# ESP_DCF77_Emulator.net
KiCad netlist of a schematic drawn in EAGLE
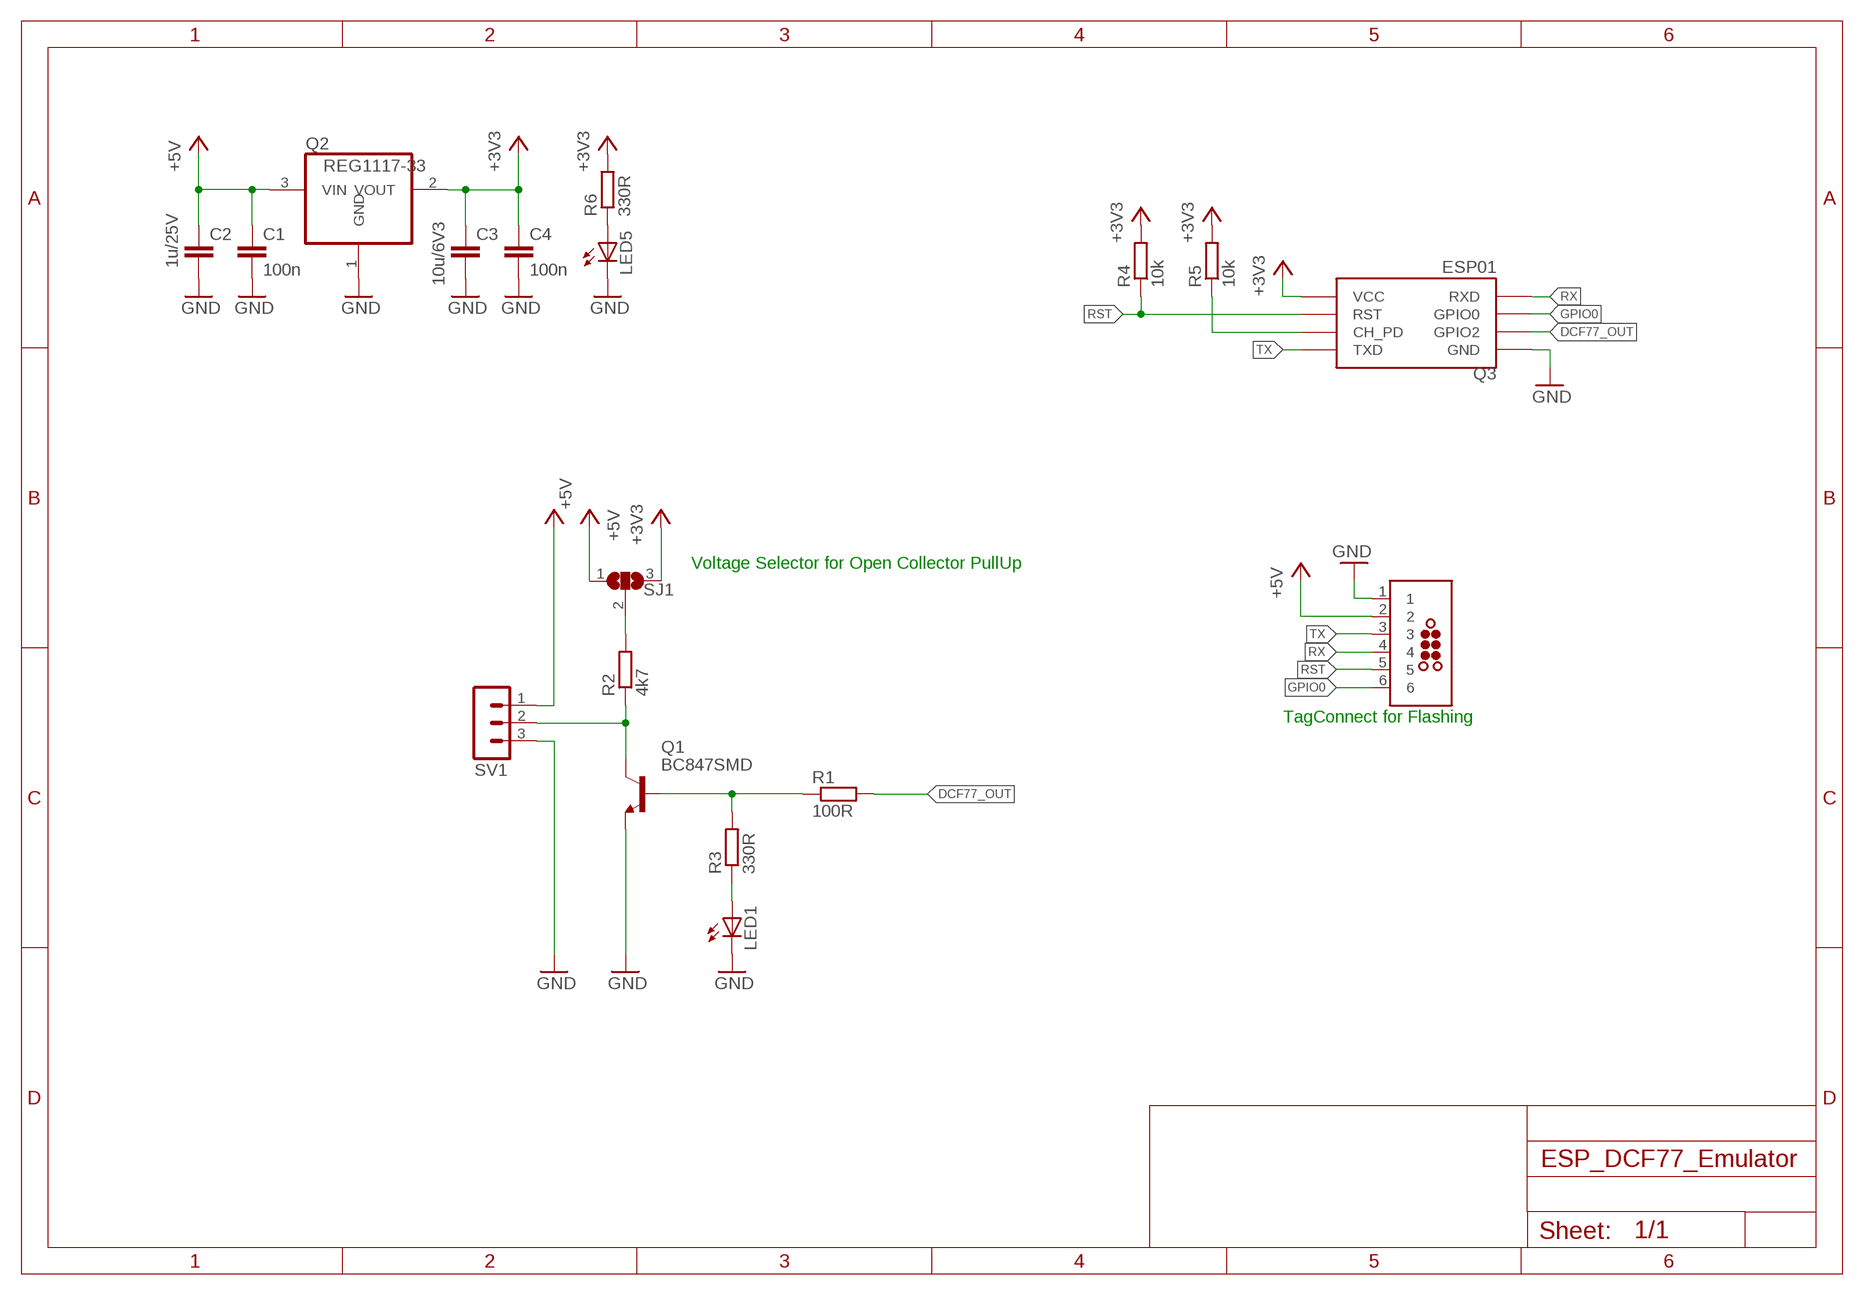
[diagram p0: schematic, sheet 1]

(export (version "E")
  (design (tool "Eeschema 10.0.6"))
  (components
    (comp (ref "C1")
      (value "100n")
      (footprint "eagle-import:C0603")
      (libsource (lib "eagle-import") (part "C-EUC0603"))
    )
    (comp (ref "C2")
      (value "1u/25V")
      (footprint "eagle-import:C0603")
      (libsource (lib "eagle-import") (part "C-EUC0603"))
    )
    (comp (ref "C3")
      (value "10u/6V3")
      (footprint "eagle-import:C0603")
      (libsource (lib "eagle-import") (part "C-EUC0603"))
    )
    (comp (ref "C4")
      (value "100n")
      (footprint "eagle-import:C0603")
      (libsource (lib "eagle-import") (part "C-EUC0603"))
    )
    (comp (ref "J6")
      (value "TC2030-MCP-NL")
      (footprint "eagle-import:TC2030-MCP-NL")
      (libsource (lib "eagle-import") (part "TC2030-MCP-NL"))
    )
    (comp (ref "LED1")
      (value "LEDCHIP-LED0603")
      (footprint "eagle-import:CHIP-LED0603")
      (libsource (lib "eagle-import") (part "LEDCHIP-LED0603"))
    )
    (comp (ref "LED5")
      (value "LEDCHIP-LED0603")
      (footprint "eagle-import:CHIP-LED0603")
      (libsource (lib "eagle-import") (part "LEDCHIP-LED0603"))
    )
    (comp (ref "Q1")
      (value "BC847SMD")
      (footprint "eagle-import:SOT23")
      (libsource (lib "eagle-import") (part "BC847SMD"))
    )
    (comp (ref "Q2")
      (value "REG1117-33")
      (footprint "eagle-import:SOT223")
      (fields (field (name "MPN") "REG1117"))
      (libsource (lib "eagle-import") (part "REG1117"))
    )
    (comp (ref "Q3")
      (value "ESP01")
      (footprint "eagle-import:ESP01")
      (libsource (lib "eagle-import") (part "ESP01"))
    )
    (comp (ref "R1")
      (value "100R")
      (footprint "eagle-import:R0603")
      (libsource (lib "eagle-import") (part "R-EU_R0603"))
    )
    (comp (ref "R2")
      (value "4k7")
      (footprint "eagle-import:R0603")
      (libsource (lib "eagle-import") (part "R-EU_R0603"))
    )
    (comp (ref "R3")
      (value "330R")
      (footprint "eagle-import:R0603")
      (libsource (lib "eagle-import") (part "R-EU_R0603"))
    )
    (comp (ref "R4")
      (value "10k")
      (footprint "eagle-import:R0603")
      (libsource (lib "eagle-import") (part "R-EU_R0603"))
    )
    (comp (ref "R5")
      (value "10k")
      (footprint "eagle-import:R0603")
      (libsource (lib "eagle-import") (part "R-EU_R0603"))
    )
    (comp (ref "R6")
      (value "330R")
      (footprint "eagle-import:R0603")
      (libsource (lib "eagle-import") (part "R-EU_R0603"))
    )
    (comp (ref "SJ1")
      (value "SJ2W")
      (footprint "eagle-import:SJ_2")
      (libsource (lib "eagle-import") (part "SJ2W"))
    )
    (comp (ref "SV1")
      (value "MA03-1")
      (footprint "eagle-import:MA03-1")
      (libsource (lib "eagle-import") (part "MA03-1"))
    )
  )
  (nets
    (net (code "1") (name "+3V3") (class "Default")
      (node (ref "C3") (pin "1") (pinfunction "1_1") (pintype "passive"))
      (node (ref "C4") (pin "1") (pinfunction "1_1") (pintype "passive"))
      (node (ref "Q2") (pin "2") (pinfunction "VOUT_2") (pintype "output"))
      (node (ref "Q3") (pin "VCC") (pinfunction "VCC_VCC") (pintype "bidirectional"))
      (node (ref "R4") (pin "2") (pinfunction "2_2") (pintype "passive"))
      (node (ref "R5") (pin "2") (pinfunction "2_2") (pintype "passive"))
      (node (ref "R6") (pin "2") (pinfunction "2_2") (pintype "passive"))
      (node (ref "SJ1") (pin "3") (pinfunction "3_3") (pintype "passive"))
    )
    (net (code "2") (name "+5V") (class "Default")
      (node (ref "C1") (pin "1") (pinfunction "1_1") (pintype "passive"))
      (node (ref "C2") (pin "1") (pinfunction "1_1") (pintype "passive"))
      (node (ref "J6") (pin "2") (pinfunction "2_2") (pintype "power_in"))
      (node (ref "Q2") (pin "3") (pinfunction "VIN_3") (pintype "input"))
      (node (ref "SJ1") (pin "1") (pinfunction "1_1") (pintype "passive"))
      (node (ref "SV1") (pin "1") (pinfunction "1_1") (pintype "passive"))
    )
    (net (code "3") (name "DCF77_OUT") (class "Default")
      (node (ref "Q3") (pin "GPIO2") (pinfunction "GPIO2_GPIO2") (pintype "bidirectional"))
      (node (ref "R1") (pin "2") (pinfunction "2_2") (pintype "passive"))
    )
    (net (code "4") (name "GND") (class "Default")
      (node (ref "C1") (pin "2") (pinfunction "2_2") (pintype "passive"))
      (node (ref "C2") (pin "2") (pinfunction "2_2") (pintype "passive"))
      (node (ref "C3") (pin "2") (pinfunction "2_2") (pintype "passive"))
      (node (ref "C4") (pin "2") (pinfunction "2_2") (pintype "passive"))
      (node (ref "J6") (pin "1") (pinfunction "1_1") (pintype "passive"))
      (node (ref "LED1") (pin "C") (pinfunction "C_C") (pintype "passive"))
      (node (ref "LED5") (pin "C") (pinfunction "C_C") (pintype "passive"))
      (node (ref "Q1") (pin "2") (pinfunction "E_2") (pintype "passive"))
      (node (ref "Q2") (pin "1") (pinfunction "GND_1") (pintype "power_in"))
      (node (ref "Q3") (pin "GND") (pinfunction "GND_GND") (pintype "bidirectional"))
      (node (ref "SV1") (pin "3") (pinfunction "3_3") (pintype "passive"))
    )
    (net (code "5") (name "GPIO0") (class "Default")
      (node (ref "J6") (pin "6") (pinfunction "6_6") (pintype "bidirectional"))
      (node (ref "Q3") (pin "GPIO0") (pinfunction "GPIO0_GPIO0") (pintype "bidirectional"))
    )
    (net (code "6") (name "Net-(LED1-PadA)") (class "Default")
      (node (ref "LED1") (pin "A") (pinfunction "A_A") (pintype "passive"))
      (node (ref "R3") (pin "1") (pinfunction "1_1") (pintype "passive"))
    )
    (net (code "7") (name "Net-(LED5-PadA)") (class "Default")
      (node (ref "LED5") (pin "A") (pinfunction "A_A") (pintype "passive"))
      (node (ref "R6") (pin "1") (pinfunction "1_1") (pintype "passive"))
    )
    (net (code "8") (name "Net-(Q1-B)") (class "Default")
      (node (ref "Q1") (pin "1") (pinfunction "B_1") (pintype "passive"))
      (node (ref "R1") (pin "1") (pinfunction "1_1") (pintype "passive"))
      (node (ref "R3") (pin "2") (pinfunction "2_2") (pintype "passive"))
    )
    (net (code "9") (name "Net-(Q1-C)") (class "Default")
      (node (ref "Q1") (pin "3") (pinfunction "C_3") (pintype "passive"))
      (node (ref "R2") (pin "1") (pinfunction "1_1") (pintype "passive"))
      (node (ref "SV1") (pin "2") (pinfunction "2_2") (pintype "passive"))
    )
    (net (code "10") (name "Net-(Q3-PadCH_PD)") (class "Default")
      (node (ref "Q3") (pin "CH_PD") (pinfunction "CH_PD_CH_PD") (pintype "bidirectional"))
      (node (ref "R5") (pin "1") (pinfunction "1_1") (pintype "passive"))
    )
    (net (code "11") (name "Net-(R2-Pad2)") (class "Default")
      (node (ref "R2") (pin "2") (pinfunction "2_2") (pintype "passive"))
      (node (ref "SJ1") (pin "2") (pinfunction "2_2") (pintype "passive"))
    )
    (net (code "12") (name "RST") (class "Default")
      (node (ref "J6") (pin "5") (pinfunction "5_5") (pintype "output"))
      (node (ref "Q3") (pin "RST") (pinfunction "RST_RST") (pintype "bidirectional"))
      (node (ref "R4") (pin "1") (pinfunction "1_1") (pintype "passive"))
    )
    (net (code "13") (name "RX") (class "Default")
      (node (ref "J6") (pin "4") (pinfunction "4_4") (pintype "bidirectional"))
      (node (ref "Q3") (pin "RX") (pinfunction "RXD_RX") (pintype "bidirectional"))
    )
    (net (code "14") (name "TX") (class "Default")
      (node (ref "J6") (pin "3") (pinfunction "3_3") (pintype "power_in"))
      (node (ref "Q3") (pin "TX") (pinfunction "TXD_TX") (pintype "bidirectional"))
    )
  )
)
